# EasyEDA-schematic-normal-version.net
KiCad netlist of a schematic drawn in EasyEDA
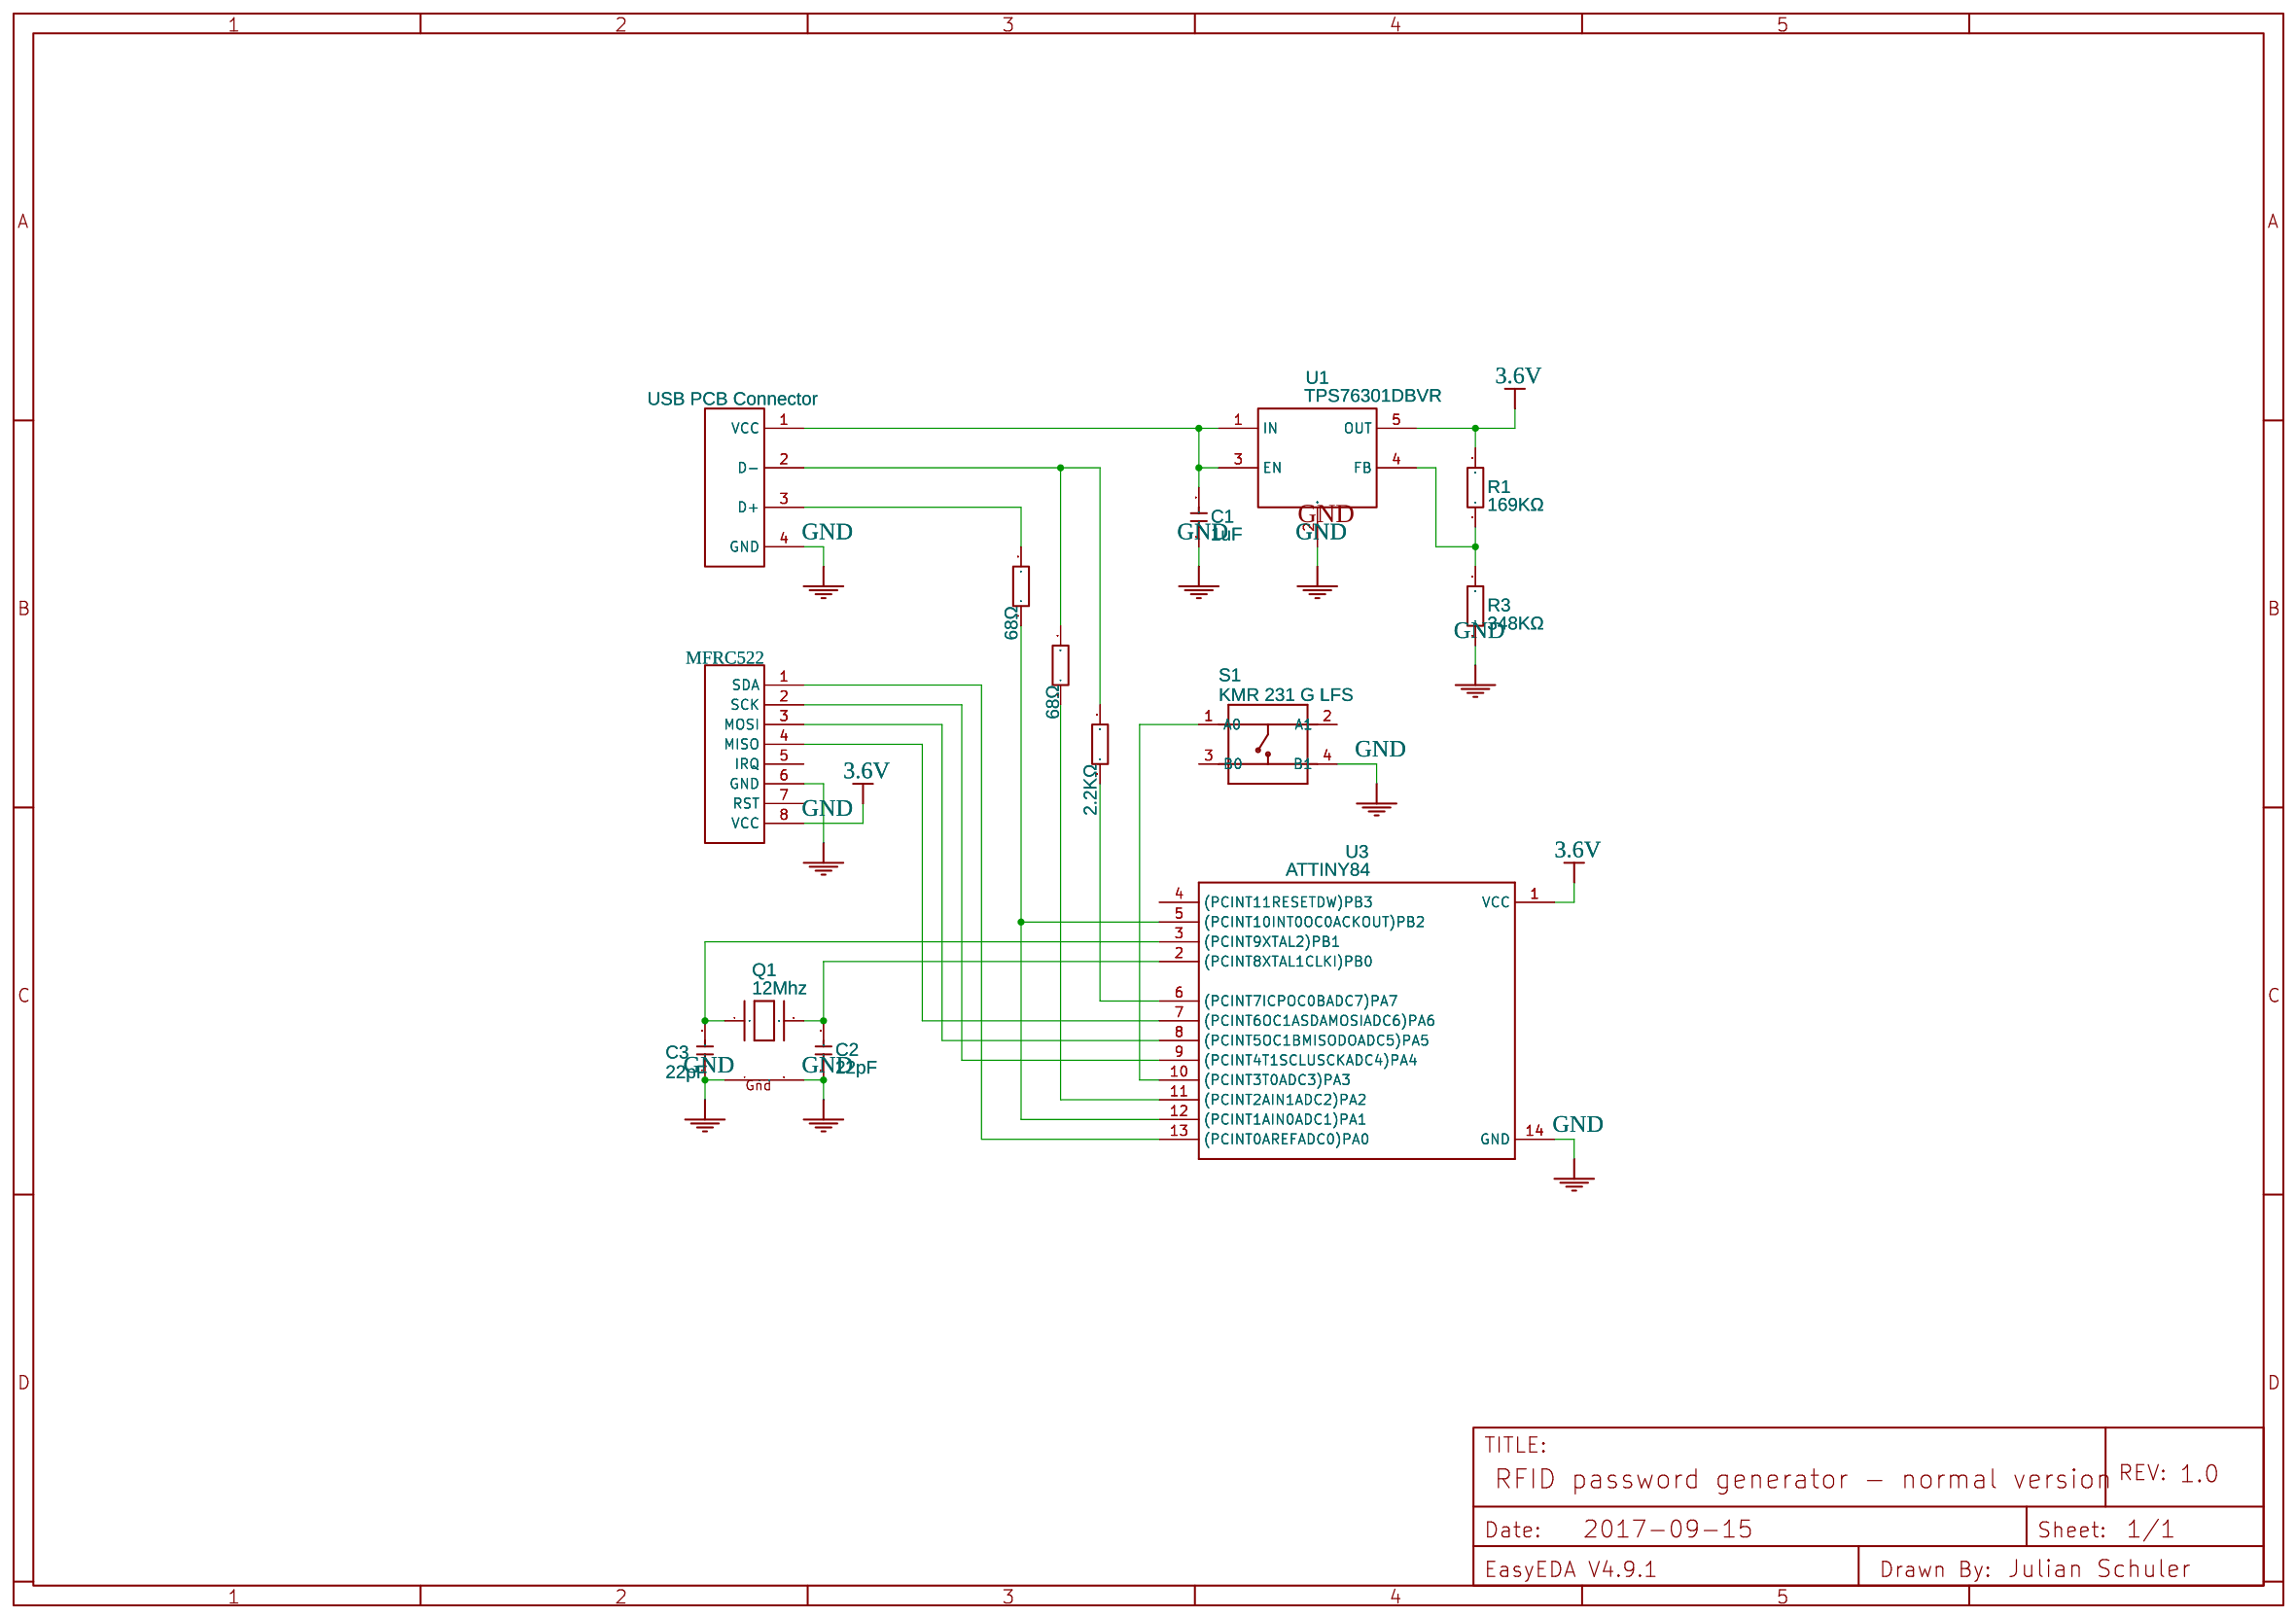
[diagram p0: schematic sheet]

(export (version "E")
  (design (tool "Eeschema 10.0.6"))
  (components
    (comp (ref "C1")
      (value "1uF")
      (fields (field (name "BOM_Manufacturer Part") "CC0805KKX7R8BB105"))
      (libsource (lib "") (part "Unknown_600_250"))
    )
    (comp (ref "C2")
      (value "22pF")
      (fields (field (name "BOM_Manufacturer Part") "CC0805JRNPO9BN220"))
      (libsource (lib "") (part "Unknown_410_520"))
    )
    (comp (ref "C3")
      (value "22pF")
      (fields (field (name "BOM_Manufacturer Part") "CC0805JRNPO9BN220"))
      (libsource (lib "") (part "Unknown_350_520"))
    )
    (comp (ref "Q1")
      (value "12Mhz")
      (fields (field (name "BOM_Manufacturer Part") "?"))
      (libsource (lib "") (part "Unknown_380_510"))
    )
    (comp (ref "R1")
      (value "169KΩ")
      (fields (field (name "BOM_Manufacturer Part") "0805W8F1693T5E"))
      (libsource (lib "") (part "Unknown_740_240"))
    )
    (comp (ref "R2")
      (value "68Ω")
      (fields (field (name "BOM_Manufacturer Part") "0805W8J0680T5E"))
      (libsource (lib "") (part "Unknown_530_330"))
    )
    (comp (ref "R3")
      (value "348KΩ")
      (fields (field (name "BOM_Manufacturer Part") "0805W8F3483T5E"))
      (libsource (lib "") (part "Unknown_740_300"))
    )
    (comp (ref "R4")
      (value "68Ω")
      (fields (field (name "BOM_Manufacturer Part") "0805W8J0680T5E"))
      (libsource (lib "") (part "Unknown_510_290"))
    )
    (comp (ref "R5")
      (value "2.2KΩ")
      (fields (field (name "BOM_Manufacturer Part") "0805W8F2201T5E"))
      (libsource (lib "") (part "Unknown_550_370"))
    )
    (comp (ref "S1")
      (value "KMR 231 G LFS")
      (fields (field (name "BOM_Manufacturer Part") "DHT-4235A"))
      (libsource (lib "") (part "Unknown_640_370"))
    )
    (comp (ref "U") (value "MFRC522") (libsource (lib "") (part "Unknown_380_370")))
    (comp (ref "U1") (value "TPS76301DBVR") (libsource (lib "") (part "Unknown_660_230")))
    (comp (ref "U2") (value "USB PCB Connector") (libsource (lib "") (part "Unknown_360_230")))
    (comp (ref "U3")
      (value "ATTINY84")
      (fields (field (name "BOM_Manufacturer Part") "?"))
      (libsource (lib "") (part "Unknown_680_510"))
    )
  )
  (nets
    (net (code "1") (name "3.6V") (class "Default")
      (node (ref "R1") (pin "2") (pinfunction "2_2") (pintype "input"))
      (node (ref "U") (pin "8") (pinfunction "VCC_8") (pintype "unspecified"))
      (node (ref "U1") (pin "5") (pinfunction "OUT_5") (pintype "passive"))
      (node (ref "U3") (pin "1") (pinfunction "VCC_1") (pintype "unspecified"))
    )
    (net (code "2") (name "GND") (class "Default")
      (node (ref "C1") (pin "1") (pinfunction "1_1") (pintype "unspecified"))
      (node (ref "C2") (pin "1") (pinfunction "1_1") (pintype "unspecified"))
      (node (ref "C3") (pin "1") (pinfunction "1_1") (pintype "unspecified"))
      (node (ref "Q1") (pin "2") (pinfunction "G2_2") (pintype "passive"))
      (node (ref "Q1") (pin "4") (pinfunction "G1_4") (pintype "passive"))
      (node (ref "R3") (pin "1") (pinfunction "1_1") (pintype "input"))
      (node (ref "S1") (pin "4") (pinfunction "B1_4") (pintype "unspecified"))
      (node (ref "U") (pin "6") (pinfunction "GND_6") (pintype "unspecified"))
      (node (ref "U1") (pin "2") (pinfunction "GND_2") (pintype "passive"))
      (node (ref "U2") (pin "4") (pinfunction "GND_4") (pintype "unspecified"))
      (node (ref "U3") (pin "14") (pinfunction "GND_14") (pintype "unspecified"))
    )
    (net (code "3") (name "Net-(Q1-X1)") (class "Default")
      (node (ref "C3") (pin "2") (pinfunction "2_2") (pintype "unspecified"))
      (node (ref "Q1") (pin "1") (pinfunction "X1_1") (pintype "unspecified"))
      (node (ref "U3") (pin "3") (pinfunction "(PCINT9XTAL2)PB1_3") (pintype "unspecified"))
    )
    (net (code "4") (name "Net-(Q1-X2)") (class "Default")
      (node (ref "C2") (pin "2") (pinfunction "2_2") (pintype "unspecified"))
      (node (ref "Q1") (pin "3") (pinfunction "X2_3") (pintype "unspecified"))
      (node (ref "U3") (pin "2") (pinfunction "(PCINT8XTAL1CLKI)PB0_2") (pintype "unspecified"))
    )
    (net (code "5") (name "Net-(S1-A0)") (class "Default")
      (node (ref "S1") (pin "1") (pinfunction "A0_1") (pintype "unspecified"))
      (node (ref "U3") (pin "10") (pinfunction "(PCINT3T0ADC3)PA3_10") (pintype "unspecified"))
    )
    (net (code "6") (name "Net-(U-MISO)") (class "Default")
      (node (ref "U") (pin "4") (pinfunction "MISO_4") (pintype "unspecified"))
      (node (ref "U3") (pin "7") (pinfunction "(PCINT6OC1ASDAMOSIADC6)PA6_7") (pintype "unspecified"))
    )
    (net (code "7") (name "Net-(U-MOSI)") (class "Default")
      (node (ref "U") (pin "3") (pinfunction "MOSI_3") (pintype "unspecified"))
      (node (ref "U3") (pin "8") (pinfunction "(PCINT5OC1BMISODOADC5)PA5_8") (pintype "unspecified"))
    )
    (net (code "8") (name "Net-(U-SCK)") (class "Default")
      (node (ref "U") (pin "2") (pinfunction "SCK_2") (pintype "unspecified"))
      (node (ref "U3") (pin "9") (pinfunction "(PCINT4T1SCLUSCKADC4)PA4_9") (pintype "unspecified"))
    )
    (net (code "9") (name "Net-(U-SDA)") (class "Default")
      (node (ref "U") (pin "1") (pinfunction "SDA_1") (pintype "unspecified"))
      (node (ref "U3") (pin "13") (pinfunction "(PCINT0AREFADC0)PA0_13") (pintype "unspecified"))
    )
    (net (code "10") (name "Net-(U1-EN)") (class "Default")
      (node (ref "C1") (pin "2") (pinfunction "2_2") (pintype "unspecified"))
      (node (ref "U1") (pin "1") (pinfunction "IN_1") (pintype "passive"))
      (node (ref "U1") (pin "3") (pinfunction "EN_3") (pintype "unspecified"))
      (node (ref "U2") (pin "1") (pinfunction "VCC_1") (pintype "unspecified"))
    )
    (net (code "11") (name "Net-(U1-FB)") (class "Default")
      (node (ref "R1") (pin "1") (pinfunction "1_1") (pintype "input"))
      (node (ref "R3") (pin "2") (pinfunction "2_2") (pintype "input"))
      (node (ref "U1") (pin "4") (pinfunction "FB_4") (pintype "unspecified"))
    )
    (net (code "12") (name "Net-(U2-D+)") (class "Default")
      (node (ref "R4") (pin "2") (pinfunction "2_2") (pintype "input"))
      (node (ref "U2") (pin "3") (pinfunction "D+_3") (pintype "unspecified"))
    )
    (net (code "13") (name "Net-(U2-D-)") (class "Default")
      (node (ref "R2") (pin "2") (pinfunction "2_2") (pintype "input"))
      (node (ref "R5") (pin "2") (pinfunction "2_2") (pintype "input"))
      (node (ref "U2") (pin "2") (pinfunction "D-_2") (pintype "unspecified"))
    )
    (net (code "14") (name "Net-(U3-(PCINT2AIN1ADC2)PA2)") (class "Default")
      (node (ref "R2") (pin "1") (pinfunction "1_1") (pintype "input"))
      (node (ref "U3") (pin "11") (pinfunction "(PCINT2AIN1ADC2)PA2_11") (pintype "unspecified"))
    )
    (net (code "15") (name "Net-(U3-(PCINT7ICPOC0BADC7)PA7)") (class "Default")
      (node (ref "R5") (pin "1") (pinfunction "1_1") (pintype "input"))
      (node (ref "U3") (pin "6") (pinfunction "(PCINT7ICPOC0BADC7)PA7_6") (pintype "unspecified"))
    )
    (net (code "16") (name "Net-(U3-(PCINT10INT0OC0ACKOUT)PB2)") (class "Default")
      (node (ref "R4") (pin "1") (pinfunction "1_1") (pintype "input"))
      (node (ref "U3") (pin "12") (pinfunction "(PCINT1AIN0ADC1)PA1_12") (pintype "unspecified"))
      (node (ref "U3") (pin "5") (pinfunction "(PCINT10INT0OC0ACKOUT)PB2_5") (pintype "unspecified"))
    )
    (net (code "17") (name "unconnected-(S1-A1-Pad2)") (class "Default")
      (node (ref "S1") (pin "2") (pinfunction "A1_2") (pintype "unspecified"))
    )
    (net (code "18") (name "unconnected-(S1-B0-Pad3)") (class "Default")
      (node (ref "S1") (pin "3") (pinfunction "B0_3") (pintype "unspecified"))
    )
    (net (code "19") (name "unconnected-(U-IRQ-Pad5)") (class "Default")
      (node (ref "U") (pin "5") (pinfunction "IRQ_5") (pintype "unspecified"))
    )
    (net (code "20") (name "unconnected-(U-RST-Pad7)") (class "Default")
      (node (ref "U") (pin "7") (pinfunction "RST_7") (pintype "unspecified"))
    )
    (net (code "21") (name "unconnected-(U3-(PCINT11RESETDW)PB3-Pad4)") (class "Default")
      (node (ref "U3") (pin "4") (pinfunction "(PCINT11RESETDW)PB3_4") (pintype "unspecified"))
    )
  )
)
